# power.net
KiCad netlist of a schematic drawn in EAGLE
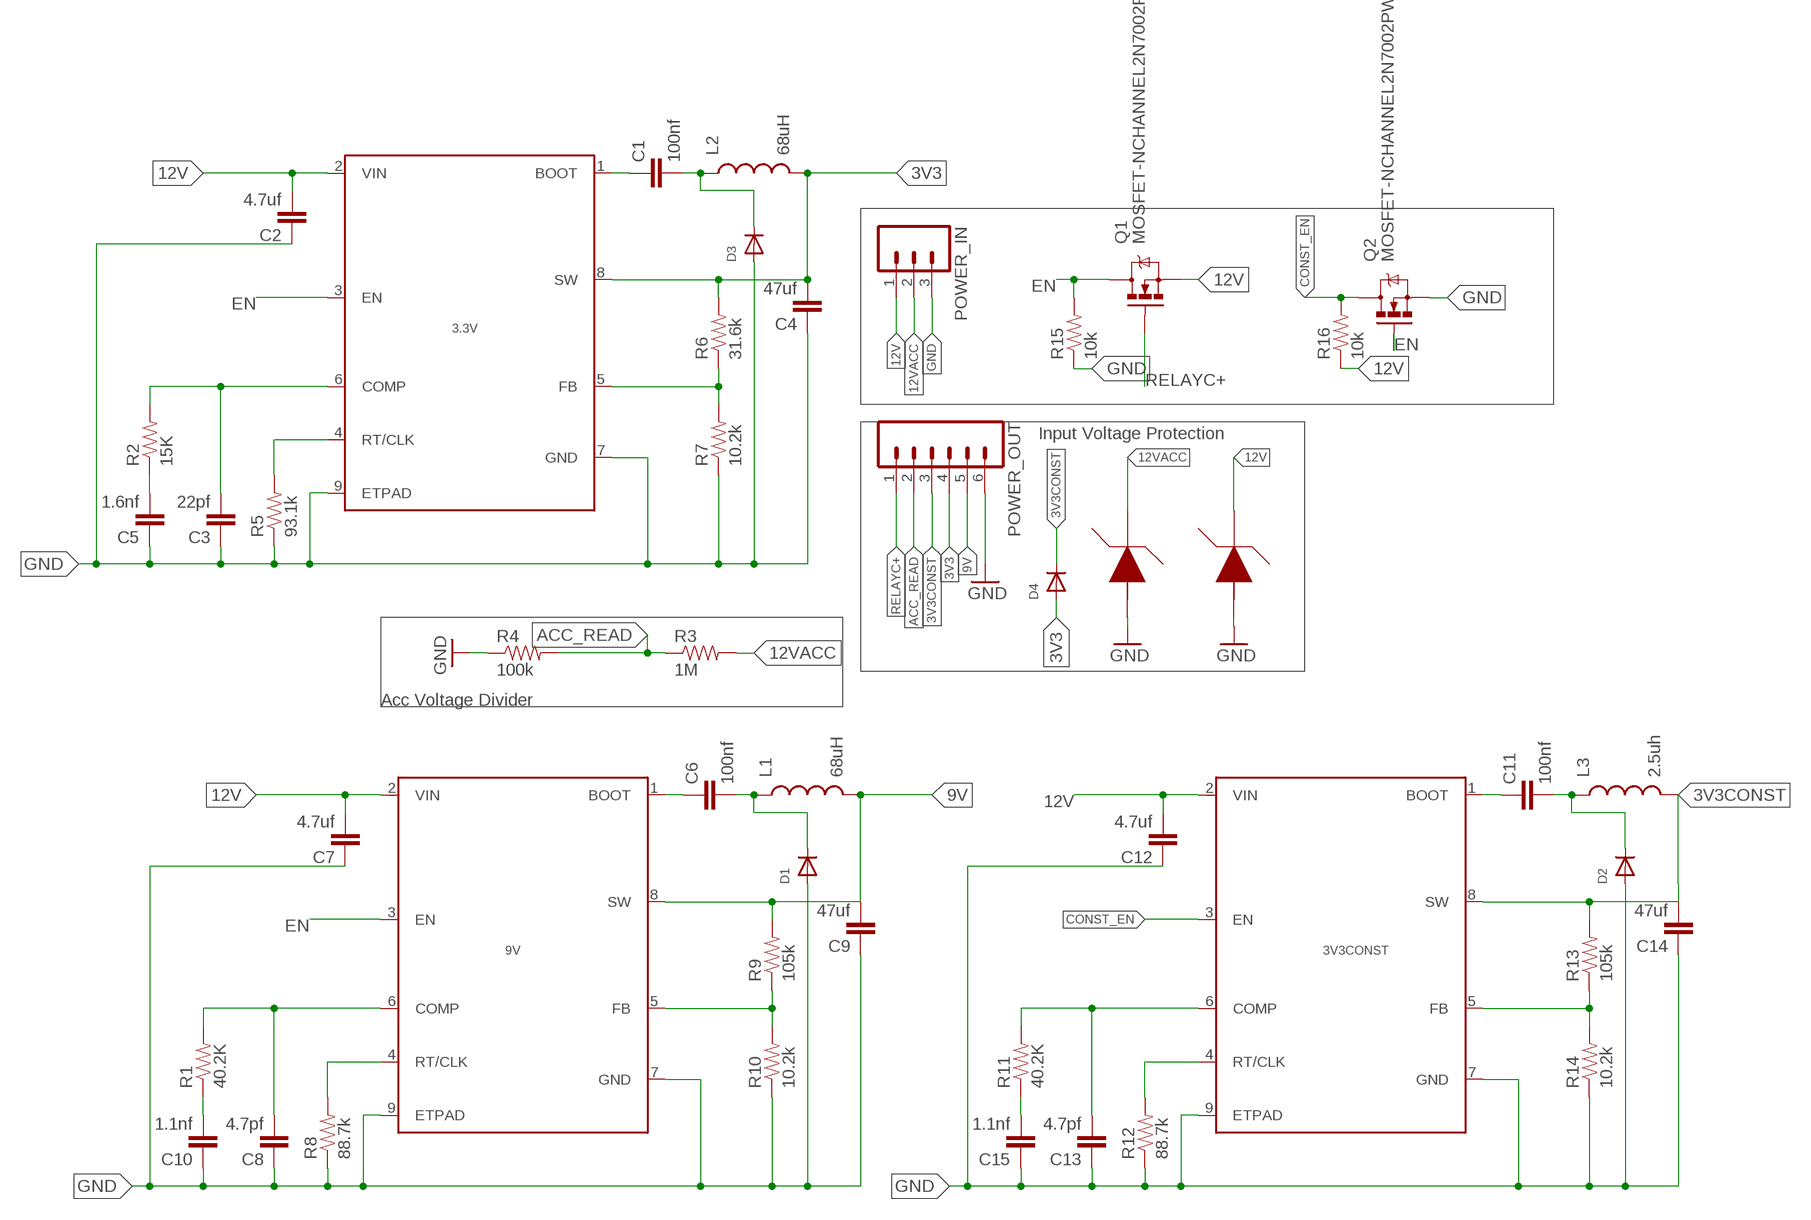
[diagram p0: schematic, sheet 1]

(export (version "E")
  (design (tool "Eeschema 10.0.6"))
  (components
    (comp (ref "3.3V")
      (value "TPS54340POWERPAD")
      (footprint "eagle-import:DDA(R-PDSO-G08)")
      (libsource (lib "eagle-import") (part "TPS54340POWERPAD"))
    )
    (comp (ref "3V3CONST")
      (value "TPS54340POWERPAD")
      (footprint "eagle-import:DDA(R-PDSO-G08)")
      (libsource (lib "eagle-import") (part "TPS54340POWERPAD"))
    )
    (comp (ref "9V")
      (value "TPS54340POWERPAD")
      (footprint "eagle-import:DDA(R-PDSO-G08)")
      (libsource (lib "eagle-import") (part "TPS54340POWERPAD"))
    )
    (comp (ref "C1")
      (value "100nf")
      (footprint "eagle-import:0603-CAP")
      (libsource (lib "eagle-import") (part "0.22UF-25V-10%(0603)"))
    )
    (comp (ref "C2")
      (value "4.7uf")
      (footprint "eagle-import:0603-CAP")
      (libsource (lib "eagle-import") (part "0.22UF-25V-10%(0603)"))
    )
    (comp (ref "C3")
      (value "22pf")
      (footprint "eagle-import:0603-CAP")
      (libsource (lib "eagle-import") (part "0.22UF-25V-10%(0603)"))
    )
    (comp (ref "C4")
      (value "47uf")
      (footprint "eagle-import:0603-CAP")
      (libsource (lib "eagle-import") (part "0.22UF-25V-10%(0603)"))
    )
    (comp (ref "C5")
      (value "1.6nf")
      (footprint "eagle-import:0603-CAP")
      (libsource (lib "eagle-import") (part "0.22UF-25V-10%(0603)"))
    )
    (comp (ref "C6")
      (value "100nf")
      (footprint "eagle-import:0603-CAP")
      (libsource (lib "eagle-import") (part "0.22UF-25V-10%(0603)"))
    )
    (comp (ref "C7")
      (value "4.7uf")
      (footprint "eagle-import:0603-CAP")
      (libsource (lib "eagle-import") (part "0.22UF-25V-10%(0603)"))
    )
    (comp (ref "C8")
      (value "4.7pf")
      (footprint "eagle-import:0603-CAP")
      (libsource (lib "eagle-import") (part "0.22UF-25V-10%(0603)"))
    )
    (comp (ref "C9")
      (value "47uf")
      (footprint "eagle-import:0603-CAP")
      (libsource (lib "eagle-import") (part "0.22UF-25V-10%(0603)"))
    )
    (comp (ref "C10")
      (value "1.1nf")
      (footprint "eagle-import:0603-CAP")
      (libsource (lib "eagle-import") (part "0.22UF-25V-10%(0603)"))
    )
    (comp (ref "C11")
      (value "100nf")
      (footprint "eagle-import:0603-CAP")
      (libsource (lib "eagle-import") (part "0.22UF-25V-10%(0603)"))
    )
    (comp (ref "C12")
      (value "4.7uf")
      (footprint "eagle-import:0603-CAP")
      (libsource (lib "eagle-import") (part "0.22UF-25V-10%(0603)"))
    )
    (comp (ref "C13")
      (value "4.7pf")
      (footprint "eagle-import:0603-CAP")
      (libsource (lib "eagle-import") (part "0.22UF-25V-10%(0603)"))
    )
    (comp (ref "C14")
      (value "47uf")
      (footprint "eagle-import:0603-CAP")
      (libsource (lib "eagle-import") (part "0.22UF-25V-10%(0603)"))
    )
    (comp (ref "C15")
      (value "1.1nf")
      (footprint "eagle-import:0603-CAP")
      (libsource (lib "eagle-import") (part "0.22UF-25V-10%(0603)"))
    )
    (comp (ref "D1")
      (value "DIODESOD-323F")
      (footprint "eagle-import:SOD-323F")
      (libsource (lib "eagle-import") (part "DIODESOD-323F"))
    )
    (comp (ref "D2")
      (value "DIODESOD-323F")
      (footprint "eagle-import:SOD-323F")
      (libsource (lib "eagle-import") (part "DIODESOD-323F"))
    )
    (comp (ref "D3")
      (value "DIODESOD-323F")
      (footprint "eagle-import:SOD-323F")
      (libsource (lib "eagle-import") (part "DIODESOD-323F"))
    )
    (comp (ref "D4")
      (value "DIODESOD-523")
      (footprint "eagle-import:SOD-523")
      (libsource (lib "eagle-import") (part "DIODESOD-523"))
    )
    (comp (ref "L1")
      (value "68uH")
      (footprint "eagle-import:CR75")
      (libsource (lib "eagle-import") (part "INDUCTOR68UH-1A"))
    )
    (comp (ref "L2")
      (value "68uH")
      (footprint "eagle-import:CR75")
      (libsource (lib "eagle-import") (part "INDUCTOR68UH-1A"))
    )
    (comp (ref "L3")
      (value "2.5uh")
      (footprint "eagle-import:CR54")
      (libsource (lib "eagle-import") (part "john_INDUCTORCR54-3.3UH"))
    )
    (comp (ref "POWER_IN")
      (value "M03")
      (footprint "eagle-import:03P")
      (libsource (lib "eagle-import") (part "M03"))
    )
    (comp (ref "POWER_OUT")
      (value "M06")
      (footprint "eagle-import:06P")
      (libsource (lib "eagle-import") (part "M06"))
    )
    (comp (ref "Q1")
      (value "MOSFET-NCHANNEL2N7002PW")
      (footprint "eagle-import:SOT323")
      (libsource (lib "eagle-import") (part "MOSFET-NCHANNEL2N7002PW"))
    )
    (comp (ref "Q2")
      (value "MOSFET-NCHANNEL2N7002PW")
      (footprint "eagle-import:SOT323")
      (libsource (lib "eagle-import") (part "MOSFET-NCHANNEL2N7002PW"))
    )
    (comp (ref "R1")
      (value "40.2K")
      (footprint "eagle-import:0603-RES")
      (libsource (lib "eagle-import") (part "RESISTOR0603"))
    )
    (comp (ref "R2")
      (value "15K")
      (footprint "eagle-import:0603-RES")
      (libsource (lib "eagle-import") (part "RESISTOR0603"))
    )
    (comp (ref "R3")
      (value "1M")
      (footprint "eagle-import:0603-RES")
      (libsource (lib "eagle-import") (part "RESISTOR0603"))
    )
    (comp (ref "R4")
      (value "100k")
      (footprint "eagle-import:0603-RES")
      (libsource (lib "eagle-import") (part "RESISTOR0603"))
    )
    (comp (ref "R5")
      (value "93.1k")
      (footprint "eagle-import:0603-RES")
      (libsource (lib "eagle-import") (part "RESISTOR0603"))
    )
    (comp (ref "R6")
      (value "31.6k")
      (footprint "eagle-import:0603-RES")
      (libsource (lib "eagle-import") (part "RESISTOR0603"))
    )
    (comp (ref "R7")
      (value "10.2k")
      (footprint "eagle-import:0603-RES")
      (libsource (lib "eagle-import") (part "RESISTOR0603"))
    )
    (comp (ref "R8")
      (value "88.7k")
      (footprint "eagle-import:0603-RES")
      (libsource (lib "eagle-import") (part "RESISTOR0603"))
    )
    (comp (ref "R9")
      (value "105k")
      (footprint "eagle-import:0603-RES")
      (libsource (lib "eagle-import") (part "RESISTOR0603"))
    )
    (comp (ref "R10")
      (value "10.2k")
      (footprint "eagle-import:0603-RES")
      (libsource (lib "eagle-import") (part "RESISTOR0603"))
    )
    (comp (ref "R11")
      (value "40.2K")
      (footprint "eagle-import:0603-RES")
      (libsource (lib "eagle-import") (part "RESISTOR0603"))
    )
    (comp (ref "R12")
      (value "88.7k")
      (footprint "eagle-import:0603-RES")
      (libsource (lib "eagle-import") (part "RESISTOR0603"))
    )
    (comp (ref "R13")
      (value "105k")
      (footprint "eagle-import:0603-RES")
      (libsource (lib "eagle-import") (part "RESISTOR0603"))
    )
    (comp (ref "R14")
      (value "10.2k")
      (footprint "eagle-import:0603-RES")
      (libsource (lib "eagle-import") (part "RESISTOR0603"))
    )
    (comp (ref "R15")
      (value "10k")
      (footprint "eagle-import:0603-RES")
      (libsource (lib "eagle-import") (part "RESISTOR0603"))
    )
    (comp (ref "R16")
      (value "10k")
      (footprint "eagle-import:0603-RES")
      (libsource (lib "eagle-import") (part "RESISTOR0603"))
    )
    (comp (ref "U$3")
      (value "SMCJ12A")
      (footprint "eagle-import:DO-214AC")
      (libsource (lib "eagle-import") (part "SMCJ12A"))
    )
    (comp (ref "U$5")
      (value "SMCJ12A")
      (footprint "eagle-import:DO-214AC")
      (libsource (lib "eagle-import") (part "SMCJ12A"))
    )
  )
  (nets
    (net (code "1") (name "/EN") (class "Default")
      (node (ref "3.3V") (pin "3") (pinfunction "EN_3") (pintype "bidirectional"))
      (node (ref "9V") (pin "3") (pinfunction "EN_3") (pintype "bidirectional"))
      (node (ref "Q1") (pin "3") (pinfunction "D_3") (pintype "passive"))
      (node (ref "Q2") (pin "1") (pinfunction "G_1") (pintype "passive"))
      (node (ref "R15") (pin "2") (pinfunction "2_2") (pintype "passive"))
    )
    (net (code "2") (name "3V3") (class "Default")
      (node (ref "3.3V") (pin "8") (pinfunction "SW_8") (pintype "bidirectional"))
      (node (ref "C4") (pin "2") (pinfunction "2_2") (pintype "passive"))
      (node (ref "D4") (pin "A") (pinfunction "A_A") (pintype "passive"))
      (node (ref "L2") (pin "P$2") (pinfunction "2_P$2") (pintype "passive"))
      (node (ref "POWER_OUT") (pin "4") (pinfunction "4_4") (pintype "passive"))
      (node (ref "R6") (pin "2") (pinfunction "2_2") (pintype "passive"))
    )
    (net (code "3") (name "3V3CONST") (class "Default")
      (node (ref "3V3CONST") (pin "8") (pinfunction "SW_8") (pintype "bidirectional"))
      (node (ref "C14") (pin "2") (pinfunction "2_2") (pintype "passive"))
      (node (ref "D4") (pin "K") (pinfunction "C_K") (pintype "passive"))
      (node (ref "L3") (pin "P$2") (pinfunction "2_P$2") (pintype "passive"))
      (node (ref "POWER_OUT") (pin "3") (pinfunction "3_3") (pintype "passive"))
      (node (ref "R13") (pin "2") (pinfunction "2_2") (pintype "passive"))
    )
    (net (code "4") (name "9V") (class "Default")
      (node (ref "9V") (pin "8") (pinfunction "SW_8") (pintype "bidirectional"))
      (node (ref "C9") (pin "2") (pinfunction "2_2") (pintype "passive"))
      (node (ref "L1") (pin "P$2") (pinfunction "2_P$2") (pintype "passive"))
      (node (ref "POWER_OUT") (pin "5") (pinfunction "5_5") (pintype "passive"))
      (node (ref "R9") (pin "2") (pinfunction "2_2") (pintype "passive"))
    )
    (net (code "5") (name "12V") (class "Default")
      (node (ref "3.3V") (pin "2") (pinfunction "VIN_2") (pintype "bidirectional"))
      (node (ref "3V3CONST") (pin "2") (pinfunction "VIN_2") (pintype "bidirectional"))
      (node (ref "9V") (pin "2") (pinfunction "VIN_2") (pintype "bidirectional"))
      (node (ref "C12") (pin "2") (pinfunction "2_2") (pintype "passive"))
      (node (ref "C2") (pin "2") (pinfunction "2_2") (pintype "passive"))
      (node (ref "C7") (pin "2") (pinfunction "2_2") (pintype "passive"))
      (node (ref "POWER_IN") (pin "1") (pinfunction "1_1") (pintype "passive"))
      (node (ref "Q1") (pin "2") (pinfunction "S_2") (pintype "passive"))
      (node (ref "R16") (pin "1") (pinfunction "1_1") (pintype "passive"))
      (node (ref "U$5") (pin "NEG") (pinfunction "GND_NEG") (pintype "bidirectional"))
    )
    (net (code "6") (name "12VACC") (class "Default")
      (node (ref "POWER_IN") (pin "2") (pinfunction "2_2") (pintype "passive"))
      (node (ref "R3") (pin "2") (pinfunction "2_2") (pintype "passive"))
      (node (ref "U$3") (pin "NEG") (pinfunction "GND_NEG") (pintype "bidirectional"))
    )
    (net (code "7") (name "ACC_READ") (class "Default")
      (node (ref "POWER_OUT") (pin "2") (pinfunction "2_2") (pintype "passive"))
      (node (ref "R3") (pin "1") (pinfunction "1_1") (pintype "passive"))
      (node (ref "R4") (pin "2") (pinfunction "2_2") (pintype "passive"))
    )
    (net (code "8") (name "CONST_EN") (class "Default")
      (node (ref "3V3CONST") (pin "3") (pinfunction "EN_3") (pintype "bidirectional"))
      (node (ref "Q2") (pin "3") (pinfunction "D_3") (pintype "passive"))
      (node (ref "R16") (pin "2") (pinfunction "2_2") (pintype "passive"))
    )
    (net (code "9") (name "GND") (class "Default")
      (node (ref "3.3V") (pin "7") (pinfunction "GND_7") (pintype "bidirectional"))
      (node (ref "3.3V") (pin "9") (pinfunction "ETPAD_9") (pintype "bidirectional"))
      (node (ref "3V3CONST") (pin "7") (pinfunction "GND_7") (pintype "bidirectional"))
      (node (ref "3V3CONST") (pin "9") (pinfunction "ETPAD_9") (pintype "bidirectional"))
      (node (ref "9V") (pin "7") (pinfunction "GND_7") (pintype "bidirectional"))
      (node (ref "9V") (pin "9") (pinfunction "ETPAD_9") (pintype "bidirectional"))
      (node (ref "C10") (pin "1") (pinfunction "1_1") (pintype "passive"))
      (node (ref "C12") (pin "1") (pinfunction "1_1") (pintype "passive"))
      (node (ref "C13") (pin "1") (pinfunction "1_1") (pintype "passive"))
      (node (ref "C14") (pin "1") (pinfunction "1_1") (pintype "passive"))
      (node (ref "C15") (pin "1") (pinfunction "1_1") (pintype "passive"))
      (node (ref "C2") (pin "1") (pinfunction "1_1") (pintype "passive"))
      (node (ref "C3") (pin "1") (pinfunction "1_1") (pintype "passive"))
      (node (ref "C4") (pin "1") (pinfunction "1_1") (pintype "passive"))
      (node (ref "C5") (pin "1") (pinfunction "1_1") (pintype "passive"))
      (node (ref "C7") (pin "1") (pinfunction "1_1") (pintype "passive"))
      (node (ref "C8") (pin "1") (pinfunction "1_1") (pintype "passive"))
      (node (ref "C9") (pin "1") (pinfunction "1_1") (pintype "passive"))
      (node (ref "D1") (pin "A") (pinfunction "A_A") (pintype "passive"))
      (node (ref "D2") (pin "A") (pinfunction "A_A") (pintype "passive"))
      (node (ref "D3") (pin "A") (pinfunction "A_A") (pintype "passive"))
      (node (ref "POWER_IN") (pin "3") (pinfunction "3_3") (pintype "passive"))
      (node (ref "POWER_OUT") (pin "6") (pinfunction "6_6") (pintype "passive"))
      (node (ref "Q2") (pin "2") (pinfunction "S_2") (pintype "passive"))
      (node (ref "R10") (pin "1") (pinfunction "1_1") (pintype "passive"))
      (node (ref "R12") (pin "1") (pinfunction "1_1") (pintype "passive"))
      (node (ref "R14") (pin "1") (pinfunction "1_1") (pintype "passive"))
      (node (ref "R15") (pin "1") (pinfunction "1_1") (pintype "passive"))
      (node (ref "R4") (pin "1") (pinfunction "1_1") (pintype "passive"))
      (node (ref "R5") (pin "1") (pinfunction "1_1") (pintype "passive"))
      (node (ref "R7") (pin "1") (pinfunction "1_1") (pintype "passive"))
      (node (ref "R8") (pin "1") (pinfunction "1_1") (pintype "passive"))
      (node (ref "U$3") (pin "POS") (pinfunction "VIN_POS") (pintype "bidirectional"))
      (node (ref "U$5") (pin "POS") (pinfunction "VIN_POS") (pintype "bidirectional"))
    )
    (net (code "10") (name "Net-(3.3V-BOOT)") (class "Default")
      (node (ref "3.3V") (pin "1") (pinfunction "BOOT_1") (pintype "bidirectional"))
      (node (ref "C1") (pin "1") (pinfunction "1_1") (pintype "passive"))
    )
    (net (code "11") (name "Net-(3.3V-COMP)") (class "Default")
      (node (ref "3.3V") (pin "6") (pinfunction "COMP_6") (pintype "bidirectional"))
      (node (ref "C3") (pin "2") (pinfunction "2_2") (pintype "passive"))
      (node (ref "R2") (pin "2") (pinfunction "2_2") (pintype "passive"))
    )
    (net (code "12") (name "Net-(3.3V-FB)") (class "Default")
      (node (ref "3.3V") (pin "5") (pinfunction "FB_5") (pintype "bidirectional"))
      (node (ref "R6") (pin "1") (pinfunction "1_1") (pintype "passive"))
      (node (ref "R7") (pin "2") (pinfunction "2_2") (pintype "passive"))
    )
    (net (code "13") (name "Net-(3.3V-RT{slash}CLK)") (class "Default")
      (node (ref "3.3V") (pin "4") (pinfunction "RT/CLK_4") (pintype "bidirectional"))
      (node (ref "R5") (pin "2") (pinfunction "2_2") (pintype "passive"))
    )
    (net (code "14") (name "Net-(3V3CONST-BOOT)") (class "Default")
      (node (ref "3V3CONST") (pin "1") (pinfunction "BOOT_1") (pintype "bidirectional"))
      (node (ref "C11") (pin "1") (pinfunction "1_1") (pintype "passive"))
    )
    (net (code "15") (name "Net-(3V3CONST-COMP)") (class "Default")
      (node (ref "3V3CONST") (pin "6") (pinfunction "COMP_6") (pintype "bidirectional"))
      (node (ref "C13") (pin "2") (pinfunction "2_2") (pintype "passive"))
      (node (ref "R11") (pin "2") (pinfunction "2_2") (pintype "passive"))
    )
    (net (code "16") (name "Net-(3V3CONST-FB)") (class "Default")
      (node (ref "3V3CONST") (pin "5") (pinfunction "FB_5") (pintype "bidirectional"))
      (node (ref "R13") (pin "1") (pinfunction "1_1") (pintype "passive"))
      (node (ref "R14") (pin "2") (pinfunction "2_2") (pintype "passive"))
    )
    (net (code "17") (name "Net-(3V3CONST-RT{slash}CLK)") (class "Default")
      (node (ref "3V3CONST") (pin "4") (pinfunction "RT/CLK_4") (pintype "bidirectional"))
      (node (ref "R12") (pin "2") (pinfunction "2_2") (pintype "passive"))
    )
    (net (code "18") (name "Net-(9V-BOOT)") (class "Default")
      (node (ref "9V") (pin "1") (pinfunction "BOOT_1") (pintype "bidirectional"))
      (node (ref "C6") (pin "1") (pinfunction "1_1") (pintype "passive"))
    )
    (net (code "19") (name "Net-(9V-COMP)") (class "Default")
      (node (ref "9V") (pin "6") (pinfunction "COMP_6") (pintype "bidirectional"))
      (node (ref "C8") (pin "2") (pinfunction "2_2") (pintype "passive"))
      (node (ref "R1") (pin "2") (pinfunction "2_2") (pintype "passive"))
    )
    (net (code "20") (name "Net-(9V-FB)") (class "Default")
      (node (ref "9V") (pin "5") (pinfunction "FB_5") (pintype "bidirectional"))
      (node (ref "R10") (pin "2") (pinfunction "2_2") (pintype "passive"))
      (node (ref "R9") (pin "1") (pinfunction "1_1") (pintype "passive"))
    )
    (net (code "21") (name "Net-(9V-RT{slash}CLK)") (class "Default")
      (node (ref "9V") (pin "4") (pinfunction "RT/CLK_4") (pintype "bidirectional"))
      (node (ref "R8") (pin "2") (pinfunction "2_2") (pintype "passive"))
    )
    (net (code "22") (name "Net-(C5-Pad2)") (class "Default")
      (node (ref "C5") (pin "2") (pinfunction "2_2") (pintype "passive"))
      (node (ref "R2") (pin "1") (pinfunction "1_1") (pintype "passive"))
    )
    (net (code "23") (name "Net-(C10-Pad2)") (class "Default")
      (node (ref "C10") (pin "2") (pinfunction "2_2") (pintype "passive"))
      (node (ref "R1") (pin "1") (pinfunction "1_1") (pintype "passive"))
    )
    (net (code "24") (name "Net-(C15-Pad2)") (class "Default")
      (node (ref "C15") (pin "2") (pinfunction "2_2") (pintype "passive"))
      (node (ref "R11") (pin "1") (pinfunction "1_1") (pintype "passive"))
    )
    (net (code "25") (name "Net-(L1-1)") (class "Default")
      (node (ref "C6") (pin "2") (pinfunction "2_2") (pintype "passive"))
      (node (ref "D1") (pin "C") (pinfunction "C_C") (pintype "passive"))
      (node (ref "L1") (pin "P$1") (pinfunction "1_P$1") (pintype "passive"))
    )
    (net (code "26") (name "Net-(L2-1)") (class "Default")
      (node (ref "C1") (pin "2") (pinfunction "2_2") (pintype "passive"))
      (node (ref "D3") (pin "C") (pinfunction "C_C") (pintype "passive"))
      (node (ref "L2") (pin "P$1") (pinfunction "1_P$1") (pintype "passive"))
    )
    (net (code "27") (name "Net-(L3-1)") (class "Default")
      (node (ref "C11") (pin "2") (pinfunction "2_2") (pintype "passive"))
      (node (ref "D2") (pin "C") (pinfunction "C_C") (pintype "passive"))
      (node (ref "L3") (pin "P$1") (pinfunction "1_P$1") (pintype "passive"))
    )
    (net (code "28") (name "RELAYC+") (class "Default")
      (node (ref "POWER_OUT") (pin "1") (pinfunction "1_1") (pintype "passive"))
      (node (ref "Q1") (pin "1") (pinfunction "G_1") (pintype "passive"))
    )
  )
)
